# PingPong_388_2019_rev4.net
KiCad netlist of a schematic drawn in EAGLE
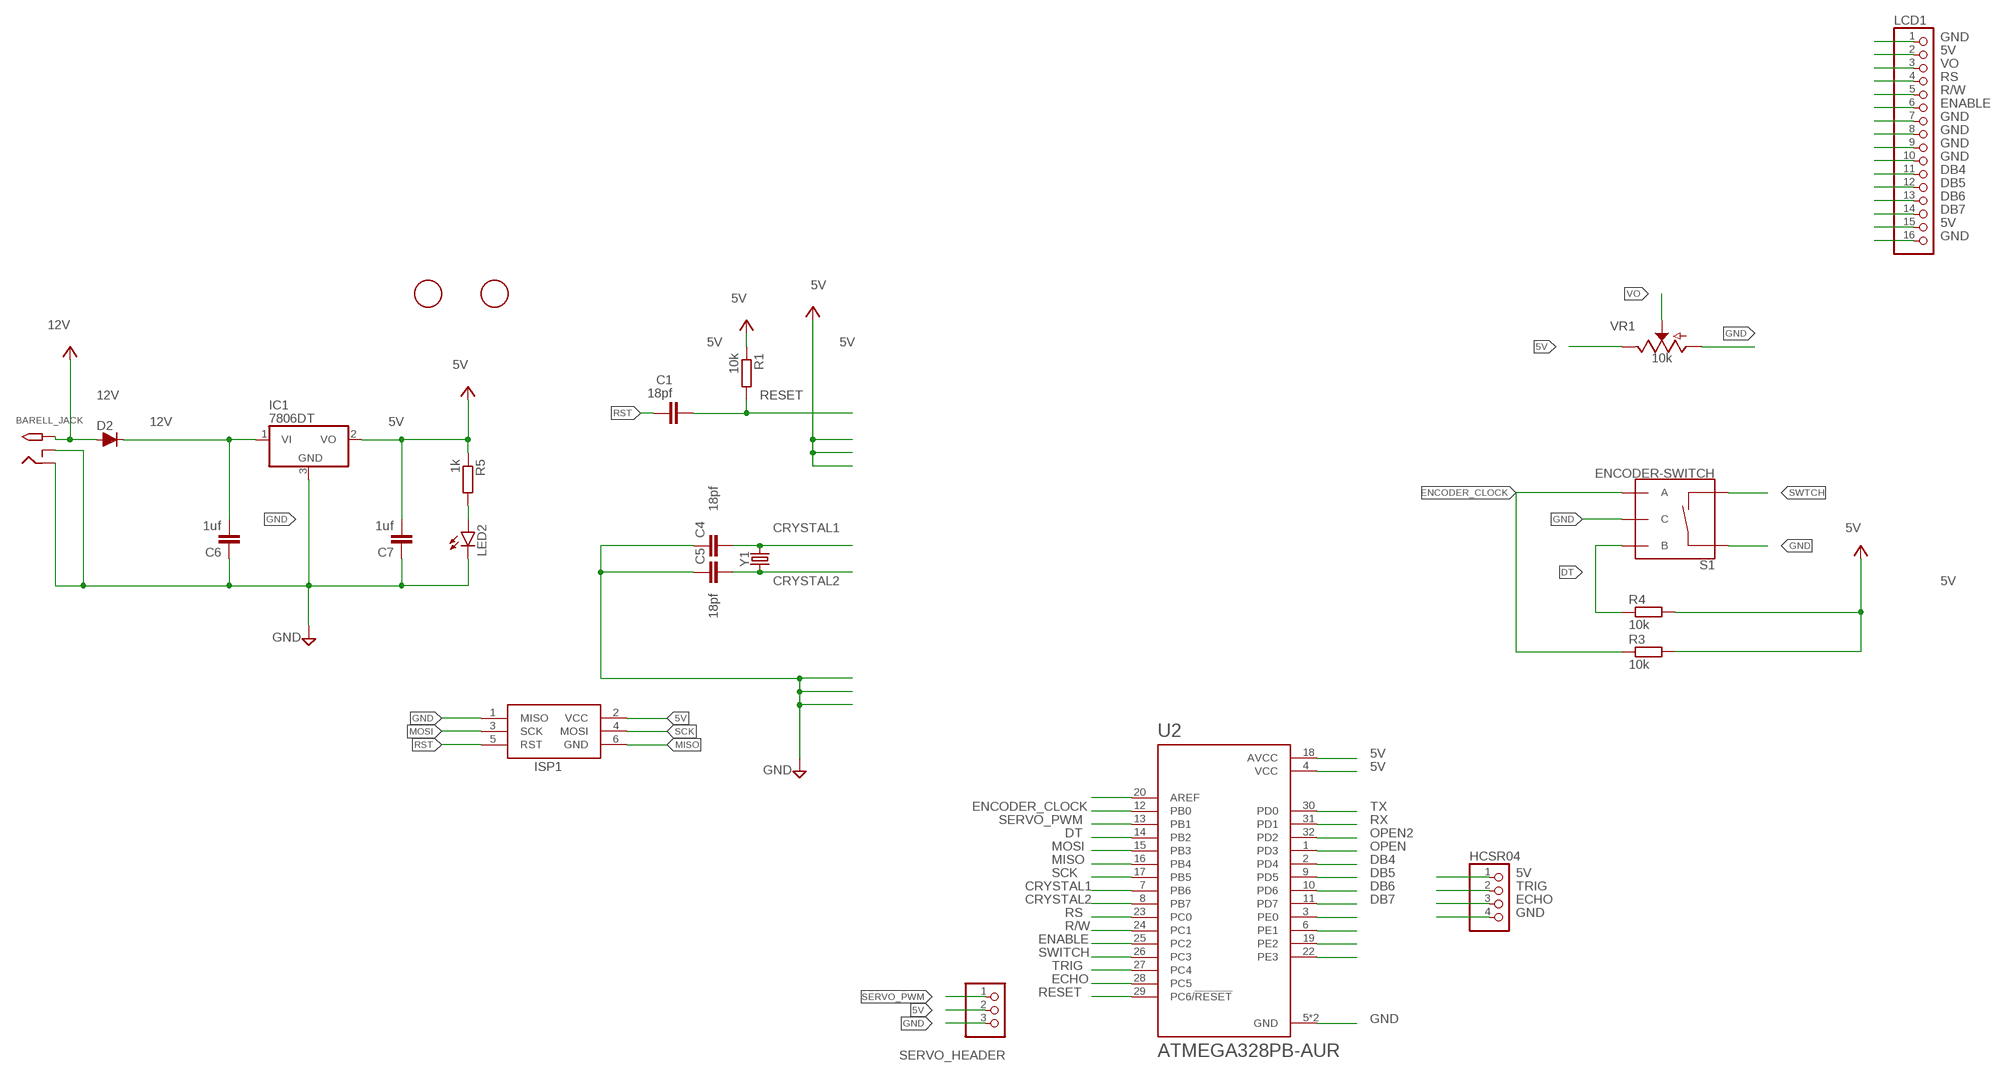
[diagram p0: schematic, sheet 1]

(export (version "E")
  (design (tool "Eeschema 10.0.6"))
  (components
    (comp (ref "BARELL_JACK")
      (value "2.1MMJACKTHM")
      (footprint "eagle-import:PJ-102A")
      (libsource (lib "eagle-import") (part "2.1MMJACKTHM"))
    )
    (comp (ref "C1")
      (value "18pf")
      (footprint "eagle-import:C0805")
      (libsource (lib "eagle-import") (part "C-EUC0805"))
    )
    (comp (ref "C4")
      (value "18pf")
      (footprint "eagle-import:C0805")
      (libsource (lib "eagle-import") (part "C-EUC0805"))
    )
    (comp (ref "C5")
      (value "18pf")
      (footprint "eagle-import:C0805")
      (libsource (lib "eagle-import") (part "C-EUC0805"))
    )
    (comp (ref "C6")
      (value "1uf")
      (footprint "eagle-import:C0805")
      (libsource (lib "eagle-import") (part "C-EUC0805"))
    )
    (comp (ref "C7")
      (value "1uf")
      (footprint "eagle-import:C0805")
      (libsource (lib "eagle-import") (part "C-EUC0805"))
    )
    (comp (ref "D2")
      (value "D-FILL-MLL-34")
      (footprint "eagle-import:MELF-MLL34")
      (libsource (lib "eagle-import") (part "D-FILL-MLL-34"))
    )
    (comp (ref "HCSR04")
      (value "PINHD-1X4")
      (footprint "eagle-import:1X04")
      (libsource (lib "eagle-import") (part "PINHD-1X4"))
    )
    (comp (ref "IC1")
      (value "7806DT")
      (footprint "eagle-import:TO252")
      (libsource (lib "eagle-import") (part "78DT06"))
    )
    (comp (ref "ISP1")
      (value "AVRISP-6")
      (footprint "eagle-import:AVRISP")
      (libsource (lib "eagle-import") (part "AVRISP-6"))
    )
    (comp (ref "LCD1")
      (value "PINHD-1X16")
      (footprint "eagle-import:1X16")
      (libsource (lib "eagle-import") (part "PINHD-1X16"))
    )
    (comp (ref "LED2")
      (value "LEDSML0805")
      (footprint "eagle-import:SML0805")
      (libsource (lib "eagle-import") (part "LEDSML0805"))
    )
    (comp (ref "R1")
      (value "10k")
      (footprint "eagle-import:R0805")
      (libsource (lib "eagle-import") (part "R-EU_R0805"))
    )
    (comp (ref "R3")
      (value "10k")
      (footprint "eagle-import:R0805")
      (libsource (lib "eagle-import") (part "R-EU_R0805"))
    )
    (comp (ref "R4")
      (value "10k")
      (footprint "eagle-import:R0805")
      (libsource (lib "eagle-import") (part "R-EU_R0805"))
    )
    (comp (ref "R5")
      (value "1k")
      (footprint "eagle-import:R0805")
      (libsource (lib "eagle-import") (part "R-EU_R0805"))
    )
    (comp (ref "S1")
      (value "ENCODER-SWITCH")
      (footprint "eagle-import:ROTARY_ENC_PLAIN")
      (libsource (lib "eagle-import") (part "ENCODER-SWITCH"))
    )
    (comp (ref "SERVO_HEADER")
      (value "PINHD-1X3")
      (footprint "eagle-import:1X03")
      (libsource (lib "eagle-import") (part "PINHD-1X3"))
    )
    (comp (ref "U$3")
      (value "FIDUCIAL")
      (footprint "eagle-import:FIDUCIAL_1MM")
      (libsource (lib "eagle-import") (part "FIDUCIAL"))
    )
    (comp (ref "U$4")
      (value "FIDUCIAL")
      (footprint "eagle-import:FIDUCIAL_1MM")
      (libsource (lib "eagle-import") (part "FIDUCIAL"))
    )
    (comp (ref "U2")
      (value "ATMEGA328PB-AUR")
      (footprint "eagle-import:QFP80P900X900X120-32N")
      (fields (field (name "MF") "Microchip"))
      (libsource (lib "eagle-import") (part "ATMEGA328PB-AUR"))
    )
    (comp (ref "VR1")
      (value "10k")
      (footprint "eagle-import:POT-PTH-ALPS")
      (libsource (lib "eagle-import") (part "POTENTIOMETER-PTH-9MM-1/20W-20%"))
    )
    (comp (ref "Y1")
      (value "CRYSTALSMD-HC49UP")
      (footprint "eagle-import:HC49UP")
      (libsource (lib "eagle-import") (part "CRYSTALSMD-HC49UP"))
    )
  )
  (nets
    (net (code "1") (name "/CRYSTAL1") (class "Default")
      (node (ref "C4") (pin "2") (pinfunction "2_2") (pintype "passive"))
      (node (ref "U2") (pin "7") (pinfunction "PB6_7") (pintype "bidirectional"))
      (node (ref "Y1") (pin "2") (pinfunction "2_2") (pintype "passive"))
    )
    (net (code "2") (name "/CRYSTAL2") (class "Default")
      (node (ref "C5") (pin "2") (pinfunction "2_2") (pintype "passive"))
      (node (ref "U2") (pin "8") (pinfunction "PB7_8") (pintype "bidirectional"))
      (node (ref "Y1") (pin "1") (pinfunction "1_1") (pintype "passive"))
    )
    (net (code "3") (name "/DB4") (class "Default")
      (node (ref "LCD1") (pin "11") (pinfunction "11_11") (pintype "passive"))
      (node (ref "U2") (pin "2") (pinfunction "PD4_2") (pintype "bidirectional"))
    )
    (net (code "4") (name "/DB5") (class "Default")
      (node (ref "LCD1") (pin "12") (pinfunction "12_12") (pintype "passive"))
      (node (ref "U2") (pin "9") (pinfunction "PD5_9") (pintype "bidirectional"))
    )
    (net (code "5") (name "/DB6") (class "Default")
      (node (ref "LCD1") (pin "13") (pinfunction "13_13") (pintype "passive"))
      (node (ref "U2") (pin "10") (pinfunction "PD6_10") (pintype "bidirectional"))
    )
    (net (code "6") (name "/DB7") (class "Default")
      (node (ref "LCD1") (pin "14") (pinfunction "14_14") (pintype "passive"))
      (node (ref "U2") (pin "11") (pinfunction "PD7_11") (pintype "bidirectional"))
    )
    (net (code "7") (name "/ECHO") (class "Default")
      (node (ref "HCSR04") (pin "3") (pinfunction "3_3") (pintype "passive"))
      (node (ref "U2") (pin "28") (pinfunction "PC5_28") (pintype "bidirectional"))
    )
    (net (code "8") (name "/ENABLE") (class "Default")
      (node (ref "LCD1") (pin "6") (pinfunction "6_6") (pintype "passive"))
      (node (ref "U2") (pin "25") (pinfunction "PC2_25") (pintype "bidirectional"))
    )
    (net (code "9") (name "/OPEN") (class "Default")
      (node (ref "U2") (pin "1") (pinfunction "PD3_1") (pintype "bidirectional"))
    )
    (net (code "10") (name "/OPEN2") (class "Default")
      (node (ref "U2") (pin "32") (pinfunction "PD2_32") (pintype "bidirectional"))
    )
    (net (code "11") (name "/RESET") (class "Default")
      (node (ref "C1") (pin "2") (pinfunction "2_2") (pintype "passive"))
      (node (ref "R1") (pin "2") (pinfunction "2_2") (pintype "passive"))
      (node (ref "U2") (pin "29") (pinfunction "PC6/~{RESET}_29") (pintype "bidirectional"))
    )
    (net (code "12") (name "/RS") (class "Default")
      (node (ref "LCD1") (pin "4") (pinfunction "4_4") (pintype "passive"))
      (node (ref "U2") (pin "23") (pinfunction "PC0_23") (pintype "bidirectional"))
    )
    (net (code "13") (name "/RX") (class "Default")
      (node (ref "U2") (pin "31") (pinfunction "PD1_31") (pintype "bidirectional"))
    )
    (net (code "14") (name "/R{slash}W") (class "Default")
      (node (ref "LCD1") (pin "5") (pinfunction "5_5") (pintype "passive"))
      (node (ref "U2") (pin "24") (pinfunction "PC1_24") (pintype "bidirectional"))
    )
    (net (code "15") (name "/SWITCH") (class "Default")
      (node (ref "U2") (pin "26") (pinfunction "PC3_26") (pintype "bidirectional"))
    )
    (net (code "16") (name "/TRIG") (class "Default")
      (node (ref "HCSR04") (pin "2") (pinfunction "2_2") (pintype "passive"))
      (node (ref "U2") (pin "27") (pinfunction "PC4_27") (pintype "bidirectional"))
    )
    (net (code "17") (name "/TX") (class "Default")
      (node (ref "U2") (pin "30") (pinfunction "PD0_30") (pintype "bidirectional"))
    )
    (net (code "18") (name "5V") (class "Default")
      (node (ref "C7") (pin "2") (pinfunction "2_2") (pintype "passive"))
      (node (ref "HCSR04") (pin "1") (pinfunction "1_1") (pintype "passive"))
      (node (ref "IC1") (pin "2") (pinfunction "VO_2") (pintype "passive"))
      (node (ref "ISP1") (pin "2") (pinfunction "VCC_2") (pintype "power_in"))
      (node (ref "LCD1") (pin "15") (pinfunction "15_15") (pintype "passive"))
      (node (ref "LCD1") (pin "2") (pinfunction "2_2") (pintype "passive"))
      (node (ref "R1") (pin "1") (pinfunction "1_1") (pintype "passive"))
      (node (ref "R3") (pin "2") (pinfunction "2_2") (pintype "passive"))
      (node (ref "R4") (pin "2") (pinfunction "2_2") (pintype "passive"))
      (node (ref "R5") (pin "1") (pinfunction "1_1") (pintype "passive"))
      (node (ref "SERVO_HEADER") (pin "2") (pinfunction "2_2") (pintype "passive"))
      (node (ref "U2") (pin "18") (pinfunction "AVCC_18") (pintype "power_in"))
      (node (ref "U2") (pin "4") (pinfunction "VCC_4") (pintype "power_in"))
      (node (ref "VR1") (pin "P$1") (pinfunction "E_P$1") (pintype "passive"))
    )
    (net (code "19") (name "12V") (class "Default")
      (node (ref "BARELL_JACK") (pin "TIP") (pinfunction "TIP_TIP") (pintype "bidirectional"))
      (node (ref "C6") (pin "2") (pinfunction "2_2") (pintype "passive"))
      (node (ref "D2") (pin "1") (pinfunction "C_1") (pintype "passive"))
      (node (ref "D2") (pin "2") (pinfunction "A_2") (pintype "passive"))
      (node (ref "IC1") (pin "1") (pinfunction "VI_1") (pintype "input"))
    )
    (net (code "20") (name "DT") (class "Default")
      (node (ref "R4") (pin "1") (pinfunction "1_1") (pintype "passive"))
      (node (ref "S1") (pin "B") (pinfunction "B_B") (pintype "bidirectional"))
      (node (ref "U2") (pin "14") (pinfunction "PB2_14") (pintype "bidirectional"))
    )
    (net (code "21") (name "ENCODER_CLOCK") (class "Default")
      (node (ref "R3") (pin "1") (pinfunction "1_1") (pintype "passive"))
      (node (ref "S1") (pin "A") (pinfunction "A_A") (pintype "bidirectional"))
      (node (ref "U2") (pin "12") (pinfunction "PB0_12") (pintype "bidirectional"))
    )
    (net (code "22") (name "GND") (class "Default")
      (node (ref "BARELL_JACK") (pin "RING") (pinfunction "RING_RING") (pintype "bidirectional"))
      (node (ref "BARELL_JACK") (pin "RING_SW") (pinfunction "RING_SW_RING_SW") (pintype "bidirectional"))
      (node (ref "C4") (pin "1") (pinfunction "1_1") (pintype "passive"))
      (node (ref "C5") (pin "1") (pinfunction "1_1") (pintype "passive"))
      (node (ref "C6") (pin "1") (pinfunction "1_1") (pintype "passive"))
      (node (ref "C7") (pin "1") (pinfunction "1_1") (pintype "passive"))
      (node (ref "HCSR04") (pin "4") (pinfunction "4_4") (pintype "passive"))
      (node (ref "IC1") (pin "3") (pinfunction "GND_3") (pintype "passive"))
      (node (ref "ISP1") (pin "1") (pinfunction "MISO_1") (pintype "input"))
      (node (ref "LCD1") (pin "1") (pinfunction "1_1") (pintype "passive"))
      (node (ref "LCD1") (pin "10") (pinfunction "10_10") (pintype "passive"))
      (node (ref "LCD1") (pin "16") (pinfunction "16_16") (pintype "passive"))
      (node (ref "LCD1") (pin "7") (pinfunction "7_7") (pintype "passive"))
      (node (ref "LCD1") (pin "8") (pinfunction "8_8") (pintype "passive"))
      (node (ref "LCD1") (pin "9") (pinfunction "9_9") (pintype "passive"))
      (node (ref "LED2") (pin "C") (pinfunction "C_C") (pintype "passive"))
      (node (ref "S1") (pin "C") (pinfunction "C_C") (pintype "bidirectional"))
      (node (ref "S1") (pin "SW+") (pinfunction "SW+_SW+") (pintype "bidirectional"))
      (node (ref "SERVO_HEADER") (pin "3") (pinfunction "3_3") (pintype "passive"))
      (node (ref "U2") (pin "21") (pinfunction "GND_21") (pintype "power_in"))
      (node (ref "U2") (pin "5") (pinfunction "GND_5") (pintype "power_in"))
      (node (ref "VR1") (pin "P$3") (pinfunction "A_P$3") (pintype "passive"))
    )
    (net (code "23") (name "MISO") (class "Default")
      (node (ref "ISP1") (pin "6") (pinfunction "GND_6") (pintype "power_in"))
      (node (ref "U2") (pin "16") (pinfunction "PB4_16") (pintype "bidirectional"))
    )
    (net (code "24") (name "MOSI") (class "Default")
      (node (ref "ISP1") (pin "3") (pinfunction "SCK_3") (pintype "output"))
      (node (ref "U2") (pin "15") (pinfunction "PB3_15") (pintype "bidirectional"))
    )
    (net (code "25") (name "Net-(LED2-PadA)") (class "Default")
      (node (ref "LED2") (pin "A") (pinfunction "A_A") (pintype "passive"))
      (node (ref "R5") (pin "2") (pinfunction "2_2") (pintype "passive"))
    )
    (net (code "26") (name "RST") (class "Default")
      (node (ref "C1") (pin "1") (pinfunction "1_1") (pintype "passive"))
      (node (ref "ISP1") (pin "5") (pinfunction "RST_5") (pintype "output"))
    )
    (net (code "27") (name "SCK") (class "Default")
      (node (ref "ISP1") (pin "4") (pinfunction "MOSI_4") (pintype "output"))
      (node (ref "U2") (pin "17") (pinfunction "PB5_17") (pintype "bidirectional"))
    )
    (net (code "28") (name "SERVO_PWM") (class "Default")
      (node (ref "SERVO_HEADER") (pin "1") (pinfunction "1_1") (pintype "passive"))
      (node (ref "U2") (pin "13") (pinfunction "PB1_13") (pintype "bidirectional"))
    )
    (net (code "29") (name "SWTCH") (class "Default")
      (node (ref "S1") (pin "SW-") (pinfunction "SW-_SW-") (pintype "bidirectional"))
    )
    (net (code "30") (name "VO") (class "Default")
      (node (ref "LCD1") (pin "3") (pinfunction "3_3") (pintype "passive"))
      (node (ref "VR1") (pin "P$2") (pinfunction "S_P$2") (pintype "passive"))
    )
    (net (code "31") (name "unconnected-(U2-AREF-Pad20)") (class "Default")
      (node (ref "U2") (pin "20") (pinfunction "AREF_20") (pintype "input"))
    )
    (net (code "32") (name "unconnected-(U2-PE0-Pad3)") (class "Default")
      (node (ref "U2") (pin "3") (pinfunction "PE0_3") (pintype "bidirectional"))
    )
    (net (code "33") (name "unconnected-(U2-PE1-Pad6)") (class "Default")
      (node (ref "U2") (pin "6") (pinfunction "PE1_6") (pintype "bidirectional"))
    )
    (net (code "34") (name "unconnected-(U2-PE2-Pad19)") (class "Default")
      (node (ref "U2") (pin "19") (pinfunction "PE2_19") (pintype "bidirectional"))
    )
    (net (code "35") (name "unconnected-(U2-PE3-Pad22)") (class "Default")
      (node (ref "U2") (pin "22") (pinfunction "PE3_22") (pintype "bidirectional"))
    )
  )
)
